# 01-MCU.net
KiCad netlist of a schematic drawn in Altium Designer
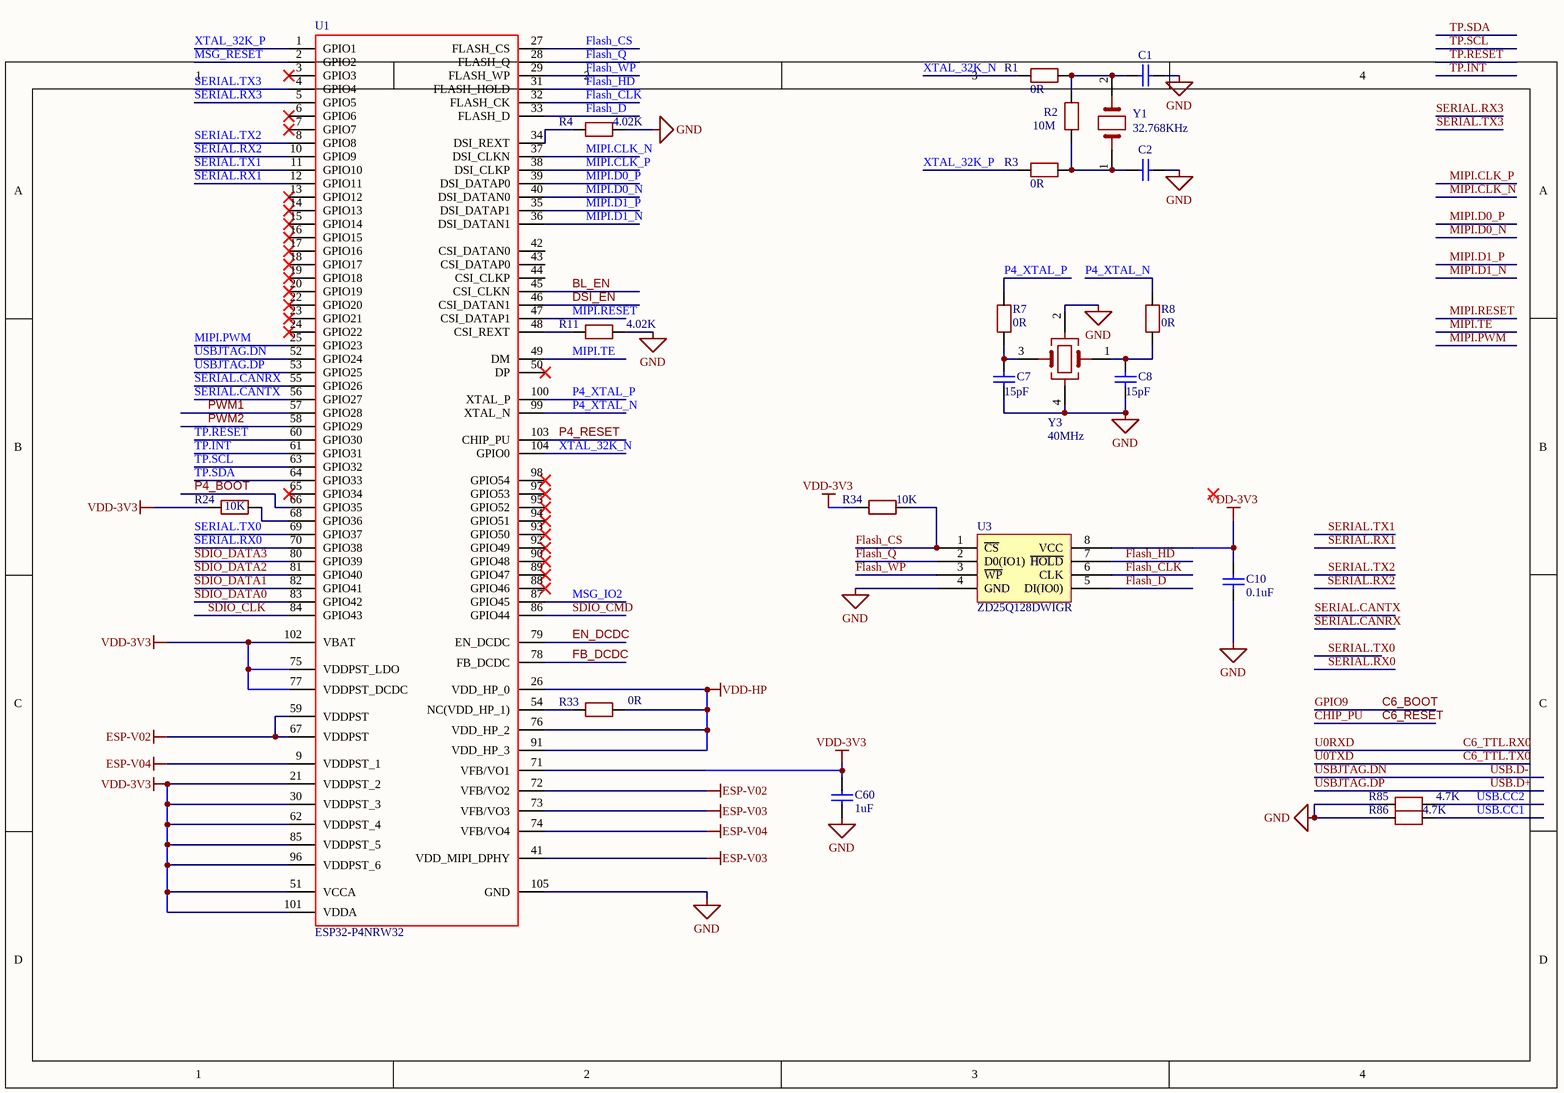
[diagram p0: 01-MCU.SchDoc]

(export (version "E")
  (design (tool "Eeschema 10.0.6"))
  (components
    (comp (ref "C1")
      (value "12.5pF")
      (footprint "C0402")
      (description "Capacitor")
      (libsource (lib "Simulation Generic Components") (part "Capacitor"))
    )
    (comp (ref "C2")
      (value "12.5pF")
      (footprint "C0402")
      (description "Capacitor")
      (libsource (lib "Simulation Generic Components") (part "Capacitor"))
    )
    (comp (ref "C7")
      (value "15pF")
      (footprint "C0402")
      (description "Capacitor")
      (libsource (lib "Simulation Generic Components") (part "Capacitor"))
    )
    (comp (ref "C8")
      (value "15pF")
      (footprint "C0402")
      (description "Capacitor")
      (libsource (lib "Simulation Generic Components") (part "Capacitor"))
    )
    (comp (ref "C10")
      (value "0.1uF")
      (footprint "C0402")
      (description "Capacitor")
      (libsource (lib "Simulation Generic Components") (part "Capacitor"))
    )
    (comp (ref "C60")
      (value "1uF")
      (footprint "C0402")
      (description "Capacitor")
      (libsource (lib "Simulation Generic Components") (part "Capacitor"))
    )
    (comp (ref "R1") (value "0R") (footprint "R0402") (libsource (lib "PCB_Project") (part "R")))
    (comp (ref "R2") (value "10M") (footprint "R0402") (libsource (lib "PCB_Project") (part "R")))
    (comp (ref "R3") (value "0R") (footprint "R0402") (libsource (lib "PCB_Project") (part "R")))
    (comp (ref "R4") (value "4.02K") (footprint "R0402") (libsource (lib "PCB_Project") (part "R")))
    (comp (ref "R7") (value "0R") (footprint "R0402") (libsource (lib "PCB_Project") (part "R")))
    (comp (ref "R8") (value "0R") (footprint "R0402") (libsource (lib "PCB_Project") (part "R")))
    (comp (ref "R11") (value "4.02K") (footprint "R0402") (libsource (lib "PCB_Project") (part "R")))
    (comp (ref "R24") (value "10K") (footprint "R0402") (libsource (lib "PCB_Project") (part "R")))
    (comp (ref "R33") (value "0R") (footprint "R0402") (libsource (lib "PCB_Project") (part "R")))
    (comp (ref "R34") (value "10K") (footprint "R0402") (libsource (lib "Schlib1") (part "R?")))
    (comp (ref "R85") (value "4.7K") (footprint "R0402") (libsource (lib "PCB_Project") (part "R")))
    (comp (ref "R86") (value "4.7K") (footprint "R0402") (libsource (lib "PCB_Project") (part "R")))
    (comp (ref "U1")
      (value "ESP32-P4NRW32")
      (footprint "QFN-104_L10.0-W10.0-P0.35-TL-EP7.5")
      (libsource (lib "PCB_Project_1") (part "ESP32-P4NRW32"))
    )
    (comp (ref "U3")
      (value "ZD25Q128DWIGR")
      (footprint "WSON-8_L6.0-W5.0-P1.27-BL-EP")
      (libsource (lib "Schlib1") (part "ZD25Q128DWIGR"))
    )
    (comp (ref "Y1")
      (value "32.768KHz")
      (footprint "CRYSTAL-SMD_L3.2-W1.5-1")
      (libsource (lib "222222") (part "Component_2"))
    )
    (comp (ref "Y3")
      (value "40MHz")
      (footprint "OSC-SMD_4P-L3.2-W2.5-BL_SIT8008BI")
      (libsource (lib "222222") (part "Component_3"))
    )
  )
  (nets
    (net (code "1") (name "/BL_EN") (class "Default")
      (node (ref "U1") (pin "45") (pinfunction "CSI_CLKN_45") (pintype "passive"))
    )
    (net (code "6") (name "/DSI_EN") (class "Default")
      (node (ref "U1") (pin "46") (pinfunction "CSI_DATAN1_46") (pintype "passive"))
    )
    (net (code "7") (name "/EN_DCDC") (class "Default")
      (node (ref "U1") (pin "79") (pinfunction "EN_DCDC_79") (pintype "passive"))
    )
    (net (code "8") (name "/FB_DCDC") (class "Default")
      (node (ref "U1") (pin "78") (pinfunction "FB_DCDC_78") (pintype "passive"))
    )
    (net (code "9") (name "/Flash_CLK") (class "Default")
      (node (ref "U1") (pin "32") (pinfunction "FLASH_CK_32") (pintype "passive"))
      (node (ref "U3") (pin "6") (pinfunction "CLK_6") (pintype "passive"))
    )
    (net (code "10") (name "/Flash_CS") (class "Default")
      (node (ref "R34") (pin "2") (pinfunction "2_2") (pintype "passive"))
      (node (ref "U1") (pin "27") (pinfunction "FLASH_CS_27") (pintype "passive"))
      (node (ref "U3") (pin "1") (pinfunction "~{CS}_1") (pintype "passive"))
    )
    (net (code "11") (name "/Flash_D") (class "Default")
      (node (ref "U1") (pin "33") (pinfunction "FLASH_D_33") (pintype "passive"))
      (node (ref "U3") (pin "5") (pinfunction "DI(IO0)_5") (pintype "passive"))
    )
    (net (code "12") (name "/Flash_HD") (class "Default")
      (node (ref "U1") (pin "31") (pinfunction "FLASH_HOLD_31") (pintype "passive"))
      (node (ref "U3") (pin "7") (pinfunction "~{HOLD}_7") (pintype "passive"))
    )
    (net (code "13") (name "/Flash_Q") (class "Default")
      (node (ref "U1") (pin "28") (pinfunction "FLASH_Q_28") (pintype "passive"))
      (node (ref "U3") (pin "2") (pinfunction "D0(IO1)_2") (pintype "passive"))
    )
    (net (code "14") (name "/Flash_WP") (class "Default")
      (node (ref "U1") (pin "29") (pinfunction "FLASH_WP_29") (pintype "passive"))
      (node (ref "U3") (pin "3") (pinfunction "~{WP}_3") (pintype "passive"))
    )
    (net (code "15") (name "/MIPI.CLK_N") (class "Default")
      (node (ref "U1") (pin "37") (pinfunction "DSI_CLKN_37") (pintype "passive"))
    )
    (net (code "16") (name "/MIPI.CLK_P") (class "Default")
      (node (ref "U1") (pin "38") (pinfunction "DSI_CLKP_38") (pintype "passive"))
    )
    (net (code "17") (name "/MIPI.D0_N") (class "Default")
      (node (ref "U1") (pin "40") (pinfunction "DSI_DATAN0_40") (pintype "passive"))
    )
    (net (code "18") (name "/MIPI.D0_P") (class "Default")
      (node (ref "U1") (pin "39") (pinfunction "DSI_DATAP0_39") (pintype "passive"))
    )
    (net (code "19") (name "/MIPI.D1_N") (class "Default")
      (node (ref "U1") (pin "36") (pinfunction "DSI_DATAN1_36") (pintype "passive"))
    )
    (net (code "20") (name "/MIPI.D1_P") (class "Default")
      (node (ref "U1") (pin "35") (pinfunction "DSI_DATAP1_35") (pintype "passive"))
    )
    (net (code "21") (name "/MIPI.PWM") (class "Default")
      (node (ref "U1") (pin "25") (pinfunction "GPIO23_25") (pintype "passive"))
    )
    (net (code "22") (name "/MIPI.RESET") (class "Default")
      (node (ref "U1") (pin "47") (pinfunction "CSI_DATAP1_47") (pintype "passive"))
    )
    (net (code "23") (name "/MIPI.TE") (class "Default")
      (node (ref "U1") (pin "49") (pinfunction "DM_49") (pintype "passive"))
    )
    (net (code "24") (name "/MSG_IO2") (class "Default")
      (node (ref "U1") (pin "87") (pinfunction "GPIO45_87") (pintype "passive"))
    )
    (net (code "25") (name "/MSG_RESET") (class "Default")
      (node (ref "U1") (pin "2") (pinfunction "GPIO2_2") (pintype "passive"))
    )
    (net (code "26") (name "/P4_BOOT") (class "Default")
      (node (ref "U1") (pin "66") (pinfunction "GPIO35_66") (pintype "passive"))
    )
    (net (code "27") (name "/P4_RESET") (class "Default")
      (node (ref "U1") (pin "103") (pinfunction "CHIP_PU_103") (pintype "passive"))
    )
    (net (code "28") (name "/P4_XTAL_N") (class "Default")
      (node (ref "R8") (pin "2") (pinfunction "2_2") (pintype "passive"))
      (node (ref "U1") (pin "99") (pinfunction "XTAL_N_99") (pintype "passive"))
    )
    (net (code "29") (name "/P4_XTAL_P") (class "Default")
      (node (ref "R7") (pin "2") (pinfunction "2_2") (pintype "passive"))
      (node (ref "U1") (pin "100") (pinfunction "XTAL_P_100") (pintype "passive"))
    )
    (net (code "30") (name "/PWM1") (class "Default")
      (node (ref "U1") (pin "57") (pinfunction "GPIO28_57") (pintype "passive"))
    )
    (net (code "31") (name "/PWM2") (class "Default")
      (node (ref "U1") (pin "58") (pinfunction "GPIO29_58") (pintype "passive"))
    )
    (net (code "32") (name "/SDIO_CLK") (class "Default")
      (node (ref "U1") (pin "84") (pinfunction "GPIO43_84") (pintype "passive"))
    )
    (net (code "33") (name "/SDIO_CMD") (class "Default")
      (node (ref "U1") (pin "86") (pinfunction "GPIO44_86") (pintype "passive"))
    )
    (net (code "34") (name "/SDIO_DATA0") (class "Default")
      (node (ref "U1") (pin "83") (pinfunction "GPIO42_83") (pintype "passive"))
    )
    (net (code "35") (name "/SDIO_DATA1") (class "Default")
      (node (ref "U1") (pin "82") (pinfunction "GPIO41_82") (pintype "passive"))
    )
    (net (code "36") (name "/SDIO_DATA2") (class "Default")
      (node (ref "U1") (pin "81") (pinfunction "GPIO40_81") (pintype "passive"))
    )
    (net (code "37") (name "/SDIO_DATA3") (class "Default")
      (node (ref "U1") (pin "80") (pinfunction "GPIO39_80") (pintype "passive"))
    )
    (net (code "38") (name "/SERIAL.CANRX") (class "Default")
      (node (ref "U1") (pin "55") (pinfunction "GPIO26_55") (pintype "passive"))
    )
    (net (code "39") (name "/SERIAL.CANTX") (class "Default")
      (node (ref "U1") (pin "56") (pinfunction "GPIO27_56") (pintype "passive"))
    )
    (net (code "40") (name "/SERIAL.RX0") (class "Default")
      (node (ref "U1") (pin "70") (pinfunction "GPIO38_70") (pintype "passive"))
    )
    (net (code "41") (name "/SERIAL.RX1") (class "Default")
      (node (ref "U1") (pin "12") (pinfunction "GPIO11_12") (pintype "passive"))
    )
    (net (code "42") (name "/SERIAL.RX2") (class "Default")
      (node (ref "U1") (pin "10") (pinfunction "GPIO9_10") (pintype "passive"))
    )
    (net (code "43") (name "/SERIAL.RX3") (class "Default")
      (node (ref "U1") (pin "5") (pinfunction "GPIO5_5") (pintype "passive"))
    )
    (net (code "44") (name "/SERIAL.TX0") (class "Default")
      (node (ref "U1") (pin "69") (pinfunction "GPIO37_69") (pintype "passive"))
    )
    (net (code "45") (name "/SERIAL.TX1") (class "Default")
      (node (ref "U1") (pin "11") (pinfunction "GPIO10_11") (pintype "passive"))
    )
    (net (code "46") (name "/SERIAL.TX2") (class "Default")
      (node (ref "U1") (pin "8") (pinfunction "GPIO8_8") (pintype "passive"))
    )
    (net (code "47") (name "/SERIAL.TX3") (class "Default")
      (node (ref "U1") (pin "4") (pinfunction "GPIO4_4") (pintype "passive"))
    )
    (net (code "48") (name "/TP.INT") (class "Default")
      (node (ref "U1") (pin "61") (pinfunction "GPIO31_61") (pintype "passive"))
    )
    (net (code "49") (name "/TP.RESET") (class "Default")
      (node (ref "U1") (pin "60") (pinfunction "GPIO30_60") (pintype "passive"))
    )
    (net (code "50") (name "/TP.SCL") (class "Default")
      (node (ref "U1") (pin "63") (pinfunction "GPIO32_63") (pintype "passive"))
    )
    (net (code "51") (name "/TP.SDA") (class "Default")
      (node (ref "U1") (pin "64") (pinfunction "GPIO33_64") (pintype "passive"))
    )
    (net (code "52") (name "/USB.CC1") (class "Default")
      (node (ref "R86") (pin "1") (pinfunction "1_1") (pintype "passive"))
    )
    (net (code "53") (name "/USB.CC2") (class "Default")
      (node (ref "R85") (pin "1") (pinfunction "1_1") (pintype "passive"))
    )
    (net (code "54") (name "/USB.D+") (class "Default")
      (node (ref "U1") (pin "53") (pinfunction "GPIO25_53") (pintype "passive"))
    )
    (net (code "55") (name "/USB.D-") (class "Default")
      (node (ref "U1") (pin "52") (pinfunction "GPIO24_52") (pintype "passive"))
    )
    (net (code "56") (name "/XTAL_32K_N") (class "Default")
      (node (ref "R1") (pin "1") (pinfunction "1_1") (pintype "passive"))
      (node (ref "U1") (pin "104") (pinfunction "GPIO0_104") (pintype "passive"))
    )
    (net (code "57") (name "/XTAL_32K_P") (class "Default")
      (node (ref "R3") (pin "1") (pinfunction "1_1") (pintype "passive"))
      (node (ref "U1") (pin "1") (pinfunction "GPIO1_1") (pintype "passive"))
    )
    (net (code "58") (name "ESP-V02") (class "Default")
      (node (ref "U1") (pin "59") (pinfunction "VDDPST_59") (pintype "passive"))
      (node (ref "U1") (pin "67") (pinfunction "VDDPST_67") (pintype "passive"))
      (node (ref "U1") (pin "72") (pinfunction "VFB/VO2_72") (pintype "passive"))
    )
    (net (code "59") (name "ESP-V03") (class "Default")
      (node (ref "U1") (pin "41") (pinfunction "VDD_MIPI_DPHY_41") (pintype "passive"))
      (node (ref "U1") (pin "73") (pinfunction "VFB/VO3_73") (pintype "passive"))
    )
    (net (code "60") (name "ESP-V04") (class "Default")
      (node (ref "U1") (pin "74") (pinfunction "VFB/VO4_74") (pintype "passive"))
      (node (ref "U1") (pin "9") (pinfunction "VDDPST_1_9") (pintype "passive"))
    )
    (net (code "61") (name "GND") (class "Default")
      (node (ref "C1") (pin "1") (pinfunction "1_1") (pintype "passive"))
      (node (ref "C10") (pin "1") (pinfunction "1_1") (pintype "passive"))
      (node (ref "C2") (pin "1") (pinfunction "1_1") (pintype "passive"))
      (node (ref "C60") (pin "1") (pinfunction "1_1") (pintype "passive"))
      (node (ref "C7") (pin "2") (pinfunction "2_2") (pintype "passive"))
      (node (ref "C8") (pin "2") (pinfunction "2_2") (pintype "passive"))
      (node (ref "R11") (pin "2") (pinfunction "2_2") (pintype "passive"))
      (node (ref "R4") (pin "2") (pinfunction "2_2") (pintype "passive"))
      (node (ref "R85") (pin "2") (pinfunction "2_2") (pintype "passive"))
      (node (ref "R86") (pin "2") (pinfunction "2_2") (pintype "passive"))
      (node (ref "U1") (pin "105") (pinfunction "GND_105") (pintype "passive"))
      (node (ref "U3") (pin "4") (pinfunction "GND_4") (pintype "passive"))
      (node (ref "Y3") (pin "2") (pinfunction "2_2") (pintype "passive"))
      (node (ref "Y3") (pin "4") (pinfunction "4_4") (pintype "passive"))
    )
    (net (code "62") (name "Net-(C1-Pad2)") (class "Default")
      (node (ref "C1") (pin "2") (pinfunction "2_2") (pintype "passive"))
      (node (ref "R1") (pin "2") (pinfunction "2_2") (pintype "passive"))
      (node (ref "R2") (pin "2") (pinfunction "2_2") (pintype "passive"))
      (node (ref "Y1") (pin "2") (pinfunction "2_2") (pintype "passive"))
    )
    (net (code "63") (name "Net-(C2-Pad2)") (class "Default")
      (node (ref "C2") (pin "2") (pinfunction "2_2") (pintype "passive"))
      (node (ref "R2") (pin "1") (pinfunction "1_1") (pintype "passive"))
      (node (ref "R3") (pin "2") (pinfunction "2_2") (pintype "passive"))
      (node (ref "Y1") (pin "1") (pinfunction "1_1") (pintype "passive"))
    )
    (net (code "64") (name "Net-(C7-Pad1)") (class "Default")
      (node (ref "C7") (pin "1") (pinfunction "1_1") (pintype "passive"))
      (node (ref "R7") (pin "1") (pinfunction "1_1") (pintype "passive"))
      (node (ref "Y3") (pin "3") (pinfunction "3_3") (pintype "passive"))
    )
    (net (code "65") (name "Net-(C8-Pad1)") (class "Default")
      (node (ref "C8") (pin "1") (pinfunction "1_1") (pintype "passive"))
      (node (ref "R8") (pin "1") (pinfunction "1_1") (pintype "passive"))
      (node (ref "Y3") (pin "1") (pinfunction "1_1") (pintype "passive"))
    )
    (net (code "66") (name "Net-(U1-CSI_REXT)") (class "Default")
      (node (ref "R11") (pin "1") (pinfunction "1_1") (pintype "passive"))
      (node (ref "U1") (pin "48") (pinfunction "CSI_REXT_48") (pintype "passive"))
    )
    (net (code "67") (name "Net-(U1-DSI_REXT)") (class "Default")
      (node (ref "R4") (pin "1") (pinfunction "1_1") (pintype "passive"))
      (node (ref "U1") (pin "34") (pinfunction "DSI_REXT_34") (pintype "passive"))
    )
    (net (code "68") (name "Net-(U1-GPIO36)") (class "Default")
      (node (ref "R24") (pin "2") (pinfunction "2_2") (pintype "passive"))
      (node (ref "U1") (pin "68") (pinfunction "GPIO36_68") (pintype "passive"))
    )
    (net (code "69") (name "Net-(U1-NC(VDD_HP_1))") (class "Default")
      (node (ref "R33") (pin "1") (pinfunction "1_1") (pintype "passive"))
      (node (ref "U1") (pin "54") (pinfunction "NC(VDD_HP_1)_54") (pintype "passive"))
    )
    (net (code "70") (name "VDD-3V3") (class "Default")
      (node (ref "C10") (pin "2") (pinfunction "2_2") (pintype "passive"))
      (node (ref "C60") (pin "2") (pinfunction "2_2") (pintype "passive"))
      (node (ref "R24") (pin "1") (pinfunction "1_1") (pintype "passive"))
      (node (ref "R34") (pin "1") (pinfunction "1_1") (pintype "passive"))
      (node (ref "U1") (pin "101") (pinfunction "VDDA_101") (pintype "passive"))
      (node (ref "U1") (pin "102") (pinfunction "VBAT_102") (pintype "passive"))
      (node (ref "U1") (pin "21") (pinfunction "VDDPST_2_21") (pintype "passive"))
      (node (ref "U1") (pin "30") (pinfunction "VDDPST_3_30") (pintype "passive"))
      (node (ref "U1") (pin "51") (pinfunction "VCCA_51") (pintype "passive"))
      (node (ref "U1") (pin "62") (pinfunction "VDDPST_4_62") (pintype "passive"))
      (node (ref "U1") (pin "71") (pinfunction "VFB/VO1_71") (pintype "passive"))
      (node (ref "U1") (pin "75") (pinfunction "VDDPST_LDO_75") (pintype "passive"))
      (node (ref "U1") (pin "77") (pinfunction "VDDPST_DCDC_77") (pintype "passive"))
      (node (ref "U1") (pin "85") (pinfunction "VDDPST_5_85") (pintype "passive"))
      (node (ref "U1") (pin "96") (pinfunction "VDDPST_6_96") (pintype "passive"))
      (node (ref "U3") (pin "8") (pinfunction "VCC_8") (pintype "passive"))
    )
    (net (code "71") (name "VDD-HP") (class "Default")
      (node (ref "R33") (pin "2") (pinfunction "2_2") (pintype "passive"))
      (node (ref "U1") (pin "26") (pinfunction "VDD_HP_0_26") (pintype "passive"))
      (node (ref "U1") (pin "76") (pinfunction "VDD_HP_2_76") (pintype "passive"))
      (node (ref "U1") (pin "91") (pinfunction "VDD_HP_3_91") (pintype "passive"))
    )
    (net (code "72") (name "unconnected-(U1-CSI_CLKP-Pad44)") (class "Default")
      (node (ref "U1") (pin "44") (pinfunction "CSI_CLKP_44") (pintype "passive"))
    )
    (net (code "73") (name "unconnected-(U1-CSI_DATAN0-Pad42)") (class "Default")
      (node (ref "U1") (pin "42") (pinfunction "CSI_DATAN0_42") (pintype "passive"))
    )
    (net (code "74") (name "unconnected-(U1-CSI_DATAP0-Pad43)") (class "Default")
      (node (ref "U1") (pin "43") (pinfunction "CSI_DATAP0_43") (pintype "passive"))
    )
    (net (code "75") (name "unconnected-(U1-DP-Pad50)") (class "Default")
      (node (ref "U1") (pin "50") (pinfunction "DP_50") (pintype "passive+no_connect"))
    )
    (net (code "76") (name "unconnected-(U1-GPIO3-Pad3)") (class "Default")
      (node (ref "U1") (pin "3") (pinfunction "GPIO3_3") (pintype "passive+no_connect"))
    )
    (net (code "77") (name "unconnected-(U1-GPIO6-Pad6)") (class "Default")
      (node (ref "U1") (pin "6") (pinfunction "GPIO6_6") (pintype "passive+no_connect"))
    )
    (net (code "78") (name "unconnected-(U1-GPIO7-Pad7)") (class "Default")
      (node (ref "U1") (pin "7") (pinfunction "GPIO7_7") (pintype "passive+no_connect"))
    )
    (net (code "79") (name "unconnected-(U1-GPIO12-Pad13)") (class "Default")
      (node (ref "U1") (pin "13") (pinfunction "GPIO12_13") (pintype "passive+no_connect"))
    )
    (net (code "80") (name "unconnected-(U1-GPIO13-Pad14)") (class "Default")
      (node (ref "U1") (pin "14") (pinfunction "GPIO13_14") (pintype "passive+no_connect"))
    )
    (net (code "81") (name "unconnected-(U1-GPIO14-Pad15)") (class "Default")
      (node (ref "U1") (pin "15") (pinfunction "GPIO14_15") (pintype "passive+no_connect"))
    )
    (net (code "82") (name "unconnected-(U1-GPIO15-Pad16)") (class "Default")
      (node (ref "U1") (pin "16") (pinfunction "GPIO15_16") (pintype "passive+no_connect"))
    )
    (net (code "83") (name "unconnected-(U1-GPIO16-Pad17)") (class "Default")
      (node (ref "U1") (pin "17") (pinfunction "GPIO16_17") (pintype "passive+no_connect"))
    )
    (net (code "84") (name "unconnected-(U1-GPIO17-Pad18)") (class "Default")
      (node (ref "U1") (pin "18") (pinfunction "GPIO17_18") (pintype "passive+no_connect"))
    )
    (net (code "85") (name "unconnected-(U1-GPIO18-Pad19)") (class "Default")
      (node (ref "U1") (pin "19") (pinfunction "GPIO18_19") (pintype "passive+no_connect"))
    )
    (net (code "86") (name "unconnected-(U1-GPIO19-Pad20)") (class "Default")
      (node (ref "U1") (pin "20") (pinfunction "GPIO19_20") (pintype "passive+no_connect"))
    )
    (net (code "87") (name "unconnected-(U1-GPIO20-Pad22)") (class "Default")
      (node (ref "U1") (pin "22") (pinfunction "GPIO20_22") (pintype "passive+no_connect"))
    )
    (net (code "88") (name "unconnected-(U1-GPIO21-Pad23)") (class "Default")
      (node (ref "U1") (pin "23") (pinfunction "GPIO21_23") (pintype "passive+no_connect"))
    )
    (net (code "89") (name "unconnected-(U1-GPIO22-Pad24)") (class "Default")
      (node (ref "U1") (pin "24") (pinfunction "GPIO22_24") (pintype "passive+no_connect"))
    )
    (net (code "90") (name "unconnected-(U1-GPIO34-Pad65)") (class "Default")
      (node (ref "U1") (pin "65") (pinfunction "GPIO34_65") (pintype "passive+no_connect"))
    )
    (net (code "91") (name "unconnected-(U1-GPIO46-Pad88)") (class "Default")
      (node (ref "U1") (pin "88") (pinfunction "GPIO46_88") (pintype "passive+no_connect"))
    )
    (net (code "92") (name "unconnected-(U1-GPIO47-Pad89)") (class "Default")
      (node (ref "U1") (pin "89") (pinfunction "GPIO47_89") (pintype "passive+no_connect"))
    )
    (net (code "93") (name "unconnected-(U1-GPIO48-Pad90)") (class "Default")
      (node (ref "U1") (pin "90") (pinfunction "GPIO48_90") (pintype "passive+no_connect"))
    )
    (net (code "94") (name "unconnected-(U1-GPIO49-Pad92)") (class "Default")
      (node (ref "U1") (pin "92") (pinfunction "GPIO49_92") (pintype "passive+no_connect"))
    )
    (net (code "95") (name "unconnected-(U1-GPIO50-Pad93)") (class "Default")
      (node (ref "U1") (pin "93") (pinfunction "GPIO50_93") (pintype "passive+no_connect"))
    )
    (net (code "96") (name "unconnected-(U1-GPIO51-Pad94)") (class "Default")
      (node (ref "U1") (pin "94") (pinfunction "GPIO51_94") (pintype "passive+no_connect"))
    )
    (net (code "97") (name "unconnected-(U1-GPIO52-Pad95)") (class "Default")
      (node (ref "U1") (pin "95") (pinfunction "GPIO52_95") (pintype "passive+no_connect"))
    )
    (net (code "98") (name "unconnected-(U1-GPIO53-Pad97)") (class "Default")
      (node (ref "U1") (pin "97") (pinfunction "GPIO53_97") (pintype "passive+no_connect"))
    )
    (net (code "99") (name "unconnected-(U1-GPIO54-Pad98)") (class "Default")
      (node (ref "U1") (pin "98") (pinfunction "GPIO54_98") (pintype "passive+no_connect"))
    )
  )
)
